# SCH_Clock_Iot.net
KiCad netlist of a schematic drawn in Altium Designer
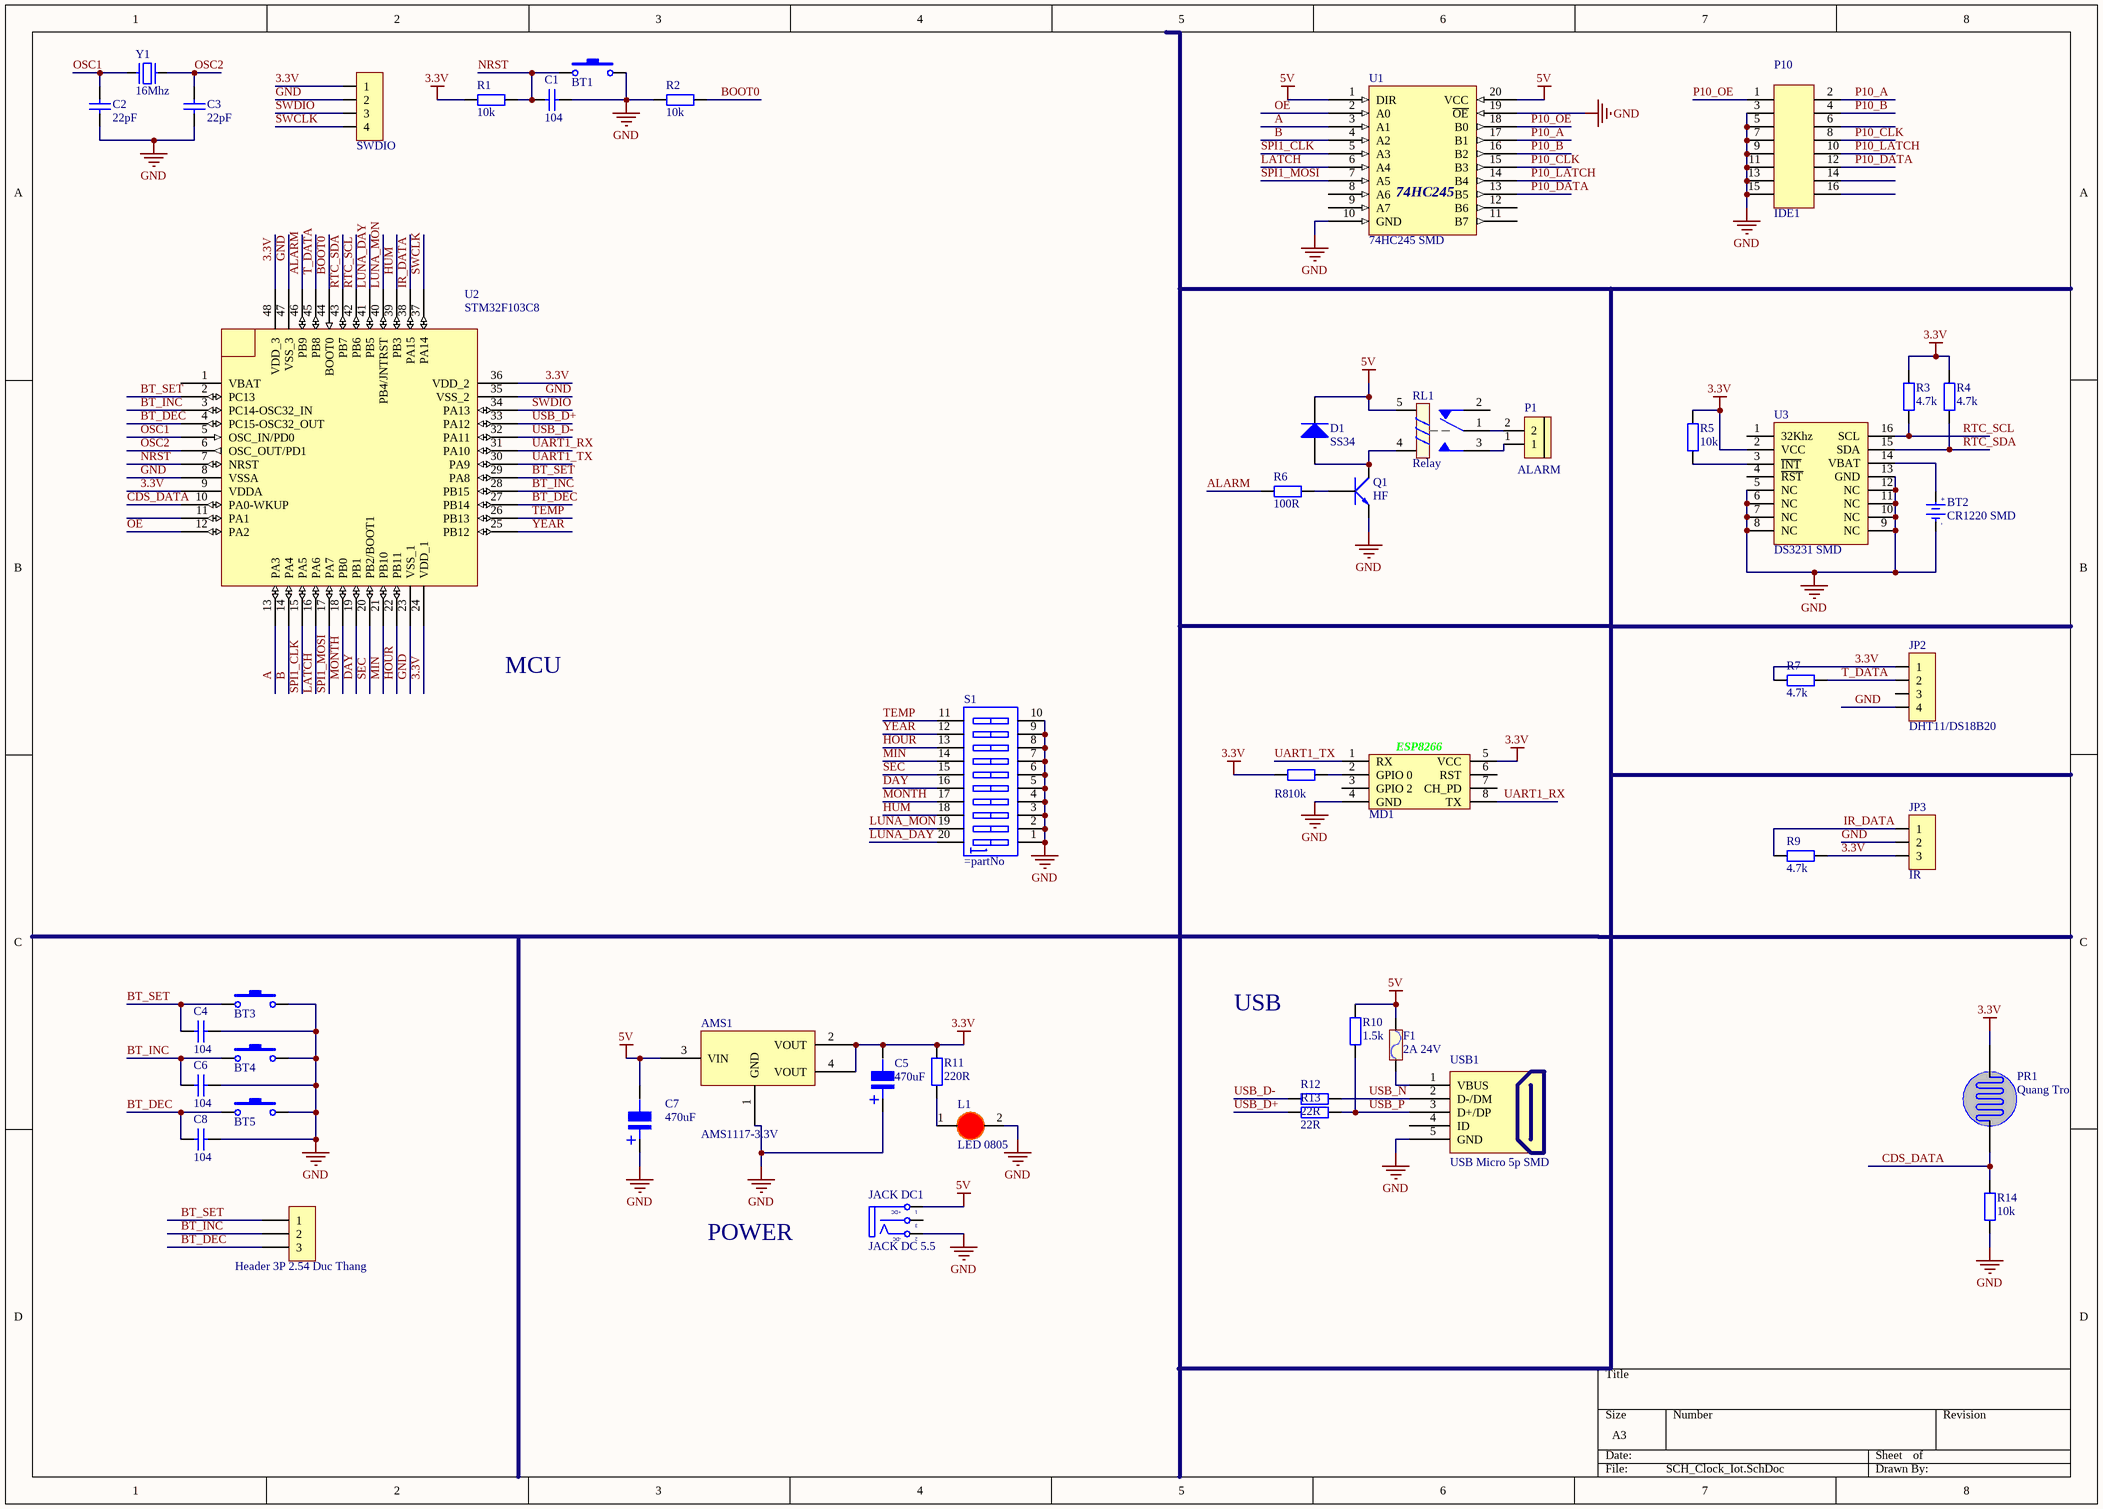
[diagram p0: SCH_Clock_Iot.SchDoc]

(export (version "E")
  (design (tool "Eeschema 10.0.6"))
  (components
    (comp (ref "AMS1")
      (value "AMS1117-3.3V")
      (footprint "SOT223")
      (description "Dán")
      (libsource (lib "Altium_Lib_by_KhueNguyenCreator") (part "AMS1117 SMD"))
    )
    (comp (ref "BT1")
      (value "Nut Nhan 2 Chan SMD 3x6x2.5")
      (footprint "Nut Nhan 2 Chan SMD 3x6x2.5")
      (libsource (lib "Altium_Lib_by_KhueNguyenCreator") (part "Nut Nhan 2 Chan SMD 3x6x2.5"))
    )
    (comp (ref "BT2")
      (value "CR1220 SMD")
      (footprint "DE PIN CR1220")
      (libsource (lib "Altium_Lib_by_KhueNguyenCreator") (part "De pin CR1220 SMD"))
    )
    (comp (ref "BT3")
      (value "Nut Nhan 2 Chan SMD 3x6x2.5")
      (footprint "Nut Nhan 2 Chan SMD 3x6x2.5")
      (libsource (lib "Altium_Lib_by_KhueNguyenCreator") (part "Nut Nhan 2 Chan SMD 3x6x2.5"))
    )
    (comp (ref "BT4")
      (value "Nut Nhan 2 Chan SMD 3x6x2.5")
      (footprint "Nut Nhan 2 Chan SMD 3x6x2.5")
      (libsource (lib "Altium_Lib_by_KhueNguyenCreator") (part "Nut Nhan 2 Chan SMD 3x6x2.5"))
    )
    (comp (ref "BT5")
      (value "Nut Nhan 2 Chan SMD 3x6x2.5")
      (footprint "Nut Nhan 2 Chan SMD 3x6x2.5")
      (libsource (lib "Altium_Lib_by_KhueNguyenCreator") (part "Nut Nhan 2 Chan SMD 3x6x2.5"))
    )
    (comp (ref "C1")
      (value "104")
      (footprint "tu 0805")
      (description "Dán")
      (libsource (lib "Altium_Lib_by_KhueNguyenCreator") (part "Tu 0805 104 50V 10%"))
    )
    (comp (ref "C2")
      (value "22pF")
      (footprint "tu 0805")
      (description "Dán")
      (libsource (lib "Altium_Lib_by_KhueNguyenCreator") (part "Tu 0805 22pF 50V 10%"))
    )
    (comp (ref "C3")
      (value "22pF")
      (footprint "tu 0805")
      (description "Dán")
      (libsource (lib "Altium_Lib_by_KhueNguyenCreator") (part "Tu 0805 22pF 50V 10%"))
    )
    (comp (ref "C4")
      (value "104")
      (footprint "tu 0805")
      (description "Dán")
      (libsource (lib "Altium_Lib_by_KhueNguyenCreator") (part "Tu 0805 104 50V 10%"))
    )
    (comp (ref "C5")
      (value "470uF")
      (footprint "tu nhom 8 (f)")
      (description "Dán")
      (libsource (lib "Altium_Lib_by_KhueNguyenCreator") (part "Tu Nhom 470uF 16V"))
    )
    (comp (ref "C6")
      (value "104")
      (footprint "tu 0805")
      (description "Dán")
      (libsource (lib "Altium_Lib_by_KhueNguyenCreator") (part "Tu 0805 104 50V 10%"))
    )
    (comp (ref "C7")
      (value "470uF")
      (footprint "tu nhom 8 (f)")
      (description "Dán")
      (libsource (lib "Altium_Lib_by_KhueNguyenCreator") (part "Tu Nhom 470uF 16V"))
    )
    (comp (ref "C8")
      (value "104")
      (footprint "tu 0805")
      (description "Dán")
      (libsource (lib "Altium_Lib_by_KhueNguyenCreator") (part "Tu 0805 104 50V 10%"))
    )
    (comp (ref "D1")
      (value "SS34")
      (footprint "DIODE SMA")
      (description "Dán")
      (libsource (lib "Altium_Lib_by_KhueNguyenCreator") (part "Diode SS34 ( 1N5822 )"))
    )
    (comp (ref "F1")
      (value "2A 24V")
      (footprint "Cau chi tu phuc hoi 2A 24V SMD1812")
      (description "2A 24V SMD1812")
      (libsource (lib "Altium_Lib_by_KhueNguyenCreator") (part "Cau chi tu phuc hoi 2A 24V SMD1812"))
    )
    (comp (ref "H1")
      (value "Header 3P 2.54 Duc Thang")
      (footprint "Header DT 3P_2.54")
      (description "Cắm")
      (libsource (lib "Altium_Lib_by_KhueNguyenCreator") (part "Header 3P 2.54 Duc Thang"))
    )
    (comp (ref "IDE1")
      (value "P10")
      (footprint "IDE16 DT")
      (libsource (lib "Altium_Lib_by_KhueNguyenCreator") (part "IDE 16 DT"))
    )
    (comp (ref "JACK DC1")
      (value "JACK DC 5.5")
      (footprint "JACK DC 5.5")
      (libsource (lib "Altium_Lib_by_KhueNguyenCreator") (part "JACK DC 5.5"))
    )
    (comp (ref "JP1")
      (value "SWDIO")
      (footprint "JP 1x4 DT")
      (description "Cắm")
      (libsource (lib "Altium_Lib_by_KhueNguyenCreator") (part "JP 1x4 2.54 Duc Thang"))
    )
    (comp (ref "JP2")
      (value "DHT11/DS18B20")
      (footprint "JP 1x4 CT")
      (description "Cắm")
      (libsource (lib "Altium_Lib_by_KhueNguyenCreator") (part "JP 1x4 2.54 Cai Thang"))
    )
    (comp (ref "JP3")
      (value "IR")
      (footprint "JP 1x3 CT")
      (description "Cắm")
      (libsource (lib "Altium_Lib_by_KhueNguyenCreator") (part "JP 1x3 2.54 Cai Thang"))
    )
    (comp (ref "L1")
      (value "LED 0805")
      (footprint "LED-0805-Red")
      (description "Dán")
      (libsource (lib "Altium_Lib_by_KhueNguyenCreator") (part "LED 0805 Do"))
    )
    (comp (ref "MD1")
      (value "ESP8266 Module")
      (footprint "ESP2866 Module")
      (libsource (lib "Altium_Lib_by_KhueNguyenCreator") (part "ESP8266 Module"))
    )
    (comp (ref "P1")
      (value "ALARM")
      (footprint "CON 2 2EDG5.08")
      (description "Cắm")
      (libsource (lib "Altium_Lib_by_KhueNguyenCreator") (part "CON 2 EDG5.08"))
    )
    (comp (ref "PR1")
      (value "Quang Tro")
      (footprint "Quang Tro")
      (description "Photoresistor")
      (fields (field (name "CREATOR") "Bien Nguyen"))
      (libsource (lib "Altium_Lib_by_KhueNguyenCreator") (part "Quang Tro"))
    )
    (comp (ref "Q1")
      (value "HF")
      (footprint "SOT23")
      (description "NPN transistor")
      (libsource (lib "Altium_Lib_by_KhueNguyenCreator") (part "C1815 HF SMD"))
    )
    (comp (ref "R1")
      (value "10k")
      (footprint "tro smd 0805")
      (description "Dán")
      (libsource (lib "Altium_Lib_by_KhueNguyenCreator") (part "Tro 0805 5% 10k"))
    )
    (comp (ref "R2")
      (value "10k")
      (footprint "tro smd 0805")
      (description "Dán")
      (libsource (lib "Altium_Lib_by_KhueNguyenCreator") (part "Tro 0805 5% 10k"))
    )
    (comp (ref "R3")
      (value "4.7k")
      (footprint "tro smd 0805")
      (description "Dán")
      (libsource (lib "Altium_Lib_by_KhueNguyenCreator") (part "Tro 0805 5% 4.7k"))
    )
    (comp (ref "R4")
      (value "4.7k")
      (footprint "tro smd 0805")
      (description "Dán")
      (libsource (lib "Altium_Lib_by_KhueNguyenCreator") (part "Tro 0805 5% 4.7k"))
    )
    (comp (ref "R5")
      (value "10k")
      (footprint "tro smd 0805")
      (description "Dán")
      (libsource (lib "Altium_Lib_by_KhueNguyenCreator") (part "Tro 0805 5% 10k"))
    )
    (comp (ref "R6")
      (value "100R")
      (footprint "tro smd 0805")
      (description "Dán")
      (libsource (lib "Altium_Lib_by_KhueNguyenCreator") (part "Tro 0805 5% 100R"))
    )
    (comp (ref "R7")
      (value "4.7k")
      (footprint "tro smd 0805")
      (description "Dán")
      (libsource (lib "Altium_Lib_by_KhueNguyenCreator") (part "Tro 0805 5% 4.7k"))
    )
    (comp (ref "R8")
      (value "10k")
      (footprint "tro smd 0805")
      (description "Dán")
      (libsource (lib "Altium_Lib_by_KhueNguyenCreator") (part "Tro 0805 5% 10k"))
    )
    (comp (ref "R9")
      (value "4.7k")
      (footprint "tro smd 0805")
      (description "Dán")
      (libsource (lib "Altium_Lib_by_KhueNguyenCreator") (part "Tro 0805 5% 4.7k"))
    )
    (comp (ref "R10")
      (value "1.5k")
      (footprint "tro smd 0805")
      (description "Dán")
      (libsource (lib "Altium_Lib_by_KhueNguyenCreator") (part "Tro 0805 5% 1.5k"))
    )
    (comp (ref "R11")
      (value "220R")
      (footprint "tro smd 0805")
      (description "Dán")
      (libsource (lib "Altium_Lib_by_KhueNguyenCreator") (part "Tro 0805 5% 220R"))
    )
    (comp (ref "R12")
      (value "22R")
      (footprint "tro smd 0805")
      (description "Dán")
      (libsource (lib "Altium_Lib_by_KhueNguyenCreator") (part "Tro 0805 5% 22R"))
    )
    (comp (ref "R13")
      (value "22R")
      (footprint "tro smd 0805")
      (description "Dán")
      (libsource (lib "Altium_Lib_by_KhueNguyenCreator") (part "Tro 0805 5% 22R"))
    )
    (comp (ref "R14")
      (value "10k")
      (footprint "tro smd 0805")
      (description "Dán")
      (libsource (lib "Altium_Lib_by_KhueNguyenCreator") (part "Tro 0805 5% 10k"))
    )
    (comp (ref "RL1")
      (value "Relay")
      (footprint "Relay 5 Chan SRD")
      (description "Relay 5 Chan")
      (libsource (lib "Altium_Lib_by_KhueNguyenCreator") (part "Relay 5 Chan SRD"))
    )
    (comp (ref "S1")
      (value "~")
      (footprint "SW-DIP10-1")
      (description "WS-DITV 2.54 mm small compact THT flat actuator with top tape")
      (fields
        (field (name "MANUFACTURER") "Wurth Elektronik")
        (field (name "PART NO.") "418127160910")
        (field (name "CREATED BY") "Baojun Chen")
      )
      (libsource (lib "Thu Vien Chuan MH") (part "SWDIP10"))
    )
    (comp (ref "U1")
      (value "74HC245 SMD")
      (footprint "TSSOP20")
      (description "Dán")
      (libsource (lib "Altium_Lib_by_KhueNguyenCreator") (part "74HC245 SMD"))
    )
    (comp (ref "U2")
      (value "STM32F103C8")
      (footprint "STM32_LQPF48")
      (fields (field (name "PUBLISHER") "Altium Limited"))
      (libsource (lib "Altium_Lib_by_KhueNguyenCreator") (part "STM32F103xx_LQFP48"))
    )
    (comp (ref "U3")
      (value "DS3231 SMD")
      (footprint "SOIC 16")
      (description "SOIC")
      (libsource (lib "Altium_Lib_by_KhueNguyenCreator") (part "DS3231 SMD"))
    )
    (comp (ref "USB1")
      (value "USB Micro 5p SMD")
      (footprint "USB Micro 5p SMD")
      (description "USB Type B")
      (libsource (lib "Altium_Lib_by_KhueNguyenCreator") (part "USB Micro 5p SMD"))
    )
    (comp (ref "Y1")
      (value "16Mhz")
      (footprint "Thach Anh 2 chan cam")
      (description "Crystal For all Crystal 2pin.")
      (libsource (lib "Altium_Lib_by_KhueNguyenCreator") (part "Thach Anh 2 chan Cam"))
    )
  )
  (nets
    (net (code "1") (name "/A") (class "Default")
      (node (ref "U1") (pin "3") (pinfunction "A1_3") (pintype "input"))
      (node (ref "U2") (pin "13") (pinfunction "PA3_13") (pintype "bidirectional"))
    )
    (net (code "2") (name "/ALARM") (class "Default")
      (node (ref "R6") (pin "1") (pinfunction "1_1") (pintype "passive"))
      (node (ref "U2") (pin "46") (pinfunction "PB9_46") (pintype "bidirectional"))
    )
    (net (code "3") (name "/B") (class "Default")
      (node (ref "U1") (pin "4") (pinfunction "A2_4") (pintype "input"))
      (node (ref "U2") (pin "14") (pinfunction "PA4_14") (pintype "bidirectional"))
    )
    (net (code "4") (name "/BOOT0") (class "Default")
      (node (ref "R2") (pin "1") (pinfunction "1_1") (pintype "passive"))
      (node (ref "U2") (pin "44") (pinfunction "BOOT0_44") (pintype "input"))
    )
    (net (code "5") (name "/BT_DEC") (class "Default")
      (node (ref "BT5") (pin "1") (pinfunction "1_1") (pintype "passive"))
      (node (ref "C8") (pin "1") (pinfunction "1_1") (pintype "passive"))
      (node (ref "H1") (pin "3") (pinfunction "3_3") (pintype "passive"))
      (node (ref "U2") (pin "27") (pinfunction "PB14_27") (pintype "bidirectional"))
      (node (ref "U2") (pin "4") (pinfunction "PC15-OSC32_OUT_4") (pintype "bidirectional"))
    )
    (net (code "6") (name "/BT_INC") (class "Default")
      (node (ref "BT4") (pin "1") (pinfunction "1_1") (pintype "passive"))
      (node (ref "C6") (pin "1") (pinfunction "1_1") (pintype "passive"))
      (node (ref "H1") (pin "2") (pinfunction "2_2") (pintype "passive"))
      (node (ref "U2") (pin "28") (pinfunction "PB15_28") (pintype "bidirectional"))
      (node (ref "U2") (pin "3") (pinfunction "PC14-OSC32_IN_3") (pintype "bidirectional"))
    )
    (net (code "7") (name "/BT_SET") (class "Default")
      (node (ref "BT3") (pin "1") (pinfunction "1_1") (pintype "passive"))
      (node (ref "C4") (pin "1") (pinfunction "1_1") (pintype "passive"))
      (node (ref "H1") (pin "1") (pinfunction "1_1") (pintype "passive"))
      (node (ref "U2") (pin "2") (pinfunction "PC13_2") (pintype "bidirectional"))
      (node (ref "U2") (pin "29") (pinfunction "PA8_29") (pintype "bidirectional"))
    )
    (net (code "8") (name "/CDS_DATA") (class "Default")
      (node (ref "PR1") (pin "1") (pinfunction "1_1") (pintype "passive"))
      (node (ref "R14") (pin "2") (pinfunction "2_2") (pintype "passive"))
      (node (ref "U2") (pin "10") (pinfunction "PA0-WKUP_10") (pintype "bidirectional"))
    )
    (net (code "9") (name "/DAY") (class "Default")
      (node (ref "S1") (pin "16") (pinfunction "16_16") (pintype "passive"))
      (node (ref "U2") (pin "19") (pinfunction "PB1_19") (pintype "bidirectional"))
    )
    (net (code "10") (name "/HOUR") (class "Default")
      (node (ref "S1") (pin "13") (pinfunction "13_13") (pintype "passive"))
      (node (ref "U2") (pin "22") (pinfunction "PB11_22") (pintype "bidirectional"))
    )
    (net (code "11") (name "/HUM") (class "Default")
      (node (ref "S1") (pin "18") (pinfunction "18_18") (pintype "passive"))
      (node (ref "U2") (pin "39") (pinfunction "PB3_39") (pintype "bidirectional"))
    )
    (net (code "12") (name "/IR_DATA") (class "Default")
      (node (ref "JP3") (pin "1") (pinfunction "1_1") (pintype "passive"))
      (node (ref "R9") (pin "2") (pinfunction "2_2") (pintype "passive"))
      (node (ref "U2") (pin "38") (pinfunction "PA15_38") (pintype "bidirectional"))
    )
    (net (code "13") (name "/LATCH") (class "Default")
      (node (ref "U1") (pin "6") (pinfunction "A4_6") (pintype "input"))
      (node (ref "U2") (pin "16") (pinfunction "PA6_16") (pintype "bidirectional"))
    )
    (net (code "14") (name "/LUNA_DAY") (class "Default")
      (node (ref "S1") (pin "20") (pinfunction "20_20") (pintype "passive"))
      (node (ref "U2") (pin "41") (pinfunction "PB5_41") (pintype "bidirectional"))
    )
    (net (code "15") (name "/LUNA_MON") (class "Default")
      (node (ref "S1") (pin "19") (pinfunction "19_19") (pintype "passive"))
      (node (ref "U2") (pin "40") (pinfunction "PB4/JNTRST_40") (pintype "bidirectional"))
    )
    (net (code "16") (name "/MIN") (class "Default")
      (node (ref "S1") (pin "14") (pinfunction "14_14") (pintype "passive"))
      (node (ref "U2") (pin "21") (pinfunction "PB10_21") (pintype "bidirectional"))
    )
    (net (code "17") (name "/MONTH") (class "Default")
      (node (ref "S1") (pin "17") (pinfunction "17_17") (pintype "passive"))
      (node (ref "U2") (pin "18") (pinfunction "PB0_18") (pintype "bidirectional"))
    )
    (net (code "18") (name "/NRST") (class "Default")
      (node (ref "BT1") (pin "1") (pinfunction "1_1") (pintype "passive"))
      (node (ref "C1") (pin "1") (pinfunction "1_1") (pintype "passive"))
      (node (ref "R1") (pin "1") (pinfunction "1_1") (pintype "passive"))
      (node (ref "U2") (pin "7") (pinfunction "NRST_7") (pintype "bidirectional"))
    )
    (net (code "19") (name "/OE") (class "Default")
      (node (ref "U1") (pin "2") (pinfunction "A0_2") (pintype "input"))
      (node (ref "U2") (pin "12") (pinfunction "PA2_12") (pintype "bidirectional"))
    )
    (net (code "20") (name "/OSC1") (class "Default")
      (node (ref "C2") (pin "1") (pinfunction "1_1") (pintype "passive"))
      (node (ref "U2") (pin "5") (pinfunction "OSC_IN/PD0_5") (pintype "input"))
      (node (ref "Y1") (pin "1") (pinfunction "1_1") (pintype "passive"))
    )
    (net (code "21") (name "/OSC2") (class "Default")
      (node (ref "C3") (pin "1") (pinfunction "1_1") (pintype "passive"))
      (node (ref "U2") (pin "6") (pinfunction "OSC_OUT/PD1_6") (pintype "output"))
      (node (ref "Y1") (pin "2") (pinfunction "2_2") (pintype "passive"))
    )
    (net (code "22") (name "/P10_A") (class "Default")
      (node (ref "IDE1") (pin "2") (pinfunction "2_2") (pintype "passive"))
      (node (ref "U1") (pin "17") (pinfunction "B1_17") (pintype "output"))
    )
    (net (code "23") (name "/P10_B") (class "Default")
      (node (ref "IDE1") (pin "4") (pinfunction "4_4") (pintype "passive"))
      (node (ref "U1") (pin "16") (pinfunction "B2_16") (pintype "output"))
    )
    (net (code "24") (name "/P10_CLK") (class "Default")
      (node (ref "IDE1") (pin "8") (pinfunction "8_8") (pintype "passive"))
      (node (ref "U1") (pin "15") (pinfunction "B3_15") (pintype "output"))
    )
    (net (code "25") (name "/P10_DATA") (class "Default")
      (node (ref "IDE1") (pin "12") (pinfunction "12_12") (pintype "passive"))
      (node (ref "U1") (pin "13") (pinfunction "B5_13") (pintype "output"))
    )
    (net (code "26") (name "/P10_LATCH") (class "Default")
      (node (ref "IDE1") (pin "10") (pinfunction "10_10") (pintype "passive"))
      (node (ref "U1") (pin "14") (pinfunction "B4_14") (pintype "output"))
    )
    (net (code "27") (name "/P10_OE") (class "Default")
      (node (ref "IDE1") (pin "1") (pinfunction "1_1") (pintype "passive"))
      (node (ref "U1") (pin "18") (pinfunction "B0_18") (pintype "output"))
    )
    (net (code "28") (name "/RTC_SCL") (class "Default")
      (node (ref "R3") (pin "1") (pinfunction "1_1") (pintype "passive"))
      (node (ref "U2") (pin "42") (pinfunction "PB6_42") (pintype "bidirectional"))
      (node (ref "U3") (pin "16") (pinfunction "SCL_16") (pintype "power_in"))
    )
    (net (code "29") (name "/RTC_SDA") (class "Default")
      (node (ref "R4") (pin "1") (pinfunction "1_1") (pintype "passive"))
      (node (ref "U2") (pin "43") (pinfunction "PB7_43") (pintype "bidirectional"))
      (node (ref "U3") (pin "15") (pinfunction "SDA_15") (pintype "power_in"))
    )
    (net (code "30") (name "/SEC") (class "Default")
      (node (ref "S1") (pin "15") (pinfunction "15_15") (pintype "passive"))
      (node (ref "U2") (pin "20") (pinfunction "PB2/BOOT1_20") (pintype "bidirectional"))
    )
    (net (code "31") (name "/SPI1_CLK") (class "Default")
      (node (ref "U1") (pin "5") (pinfunction "A3_5") (pintype "input"))
      (node (ref "U2") (pin "15") (pinfunction "PA5_15") (pintype "bidirectional"))
    )
    (net (code "32") (name "/SPI1_MOSI") (class "Default")
      (node (ref "U1") (pin "7") (pinfunction "A5_7") (pintype "input"))
      (node (ref "U2") (pin "17") (pinfunction "PA7_17") (pintype "bidirectional"))
    )
    (net (code "33") (name "/SWCLK") (class "Default")
      (node (ref "JP1") (pin "4") (pinfunction "4_4") (pintype "passive"))
      (node (ref "U2") (pin "37") (pinfunction "PA14_37") (pintype "bidirectional"))
    )
    (net (code "34") (name "/SWDIO") (class "Default")
      (node (ref "JP1") (pin "3") (pinfunction "3_3") (pintype "passive"))
      (node (ref "U2") (pin "34") (pinfunction "PA13_34") (pintype "bidirectional"))
    )
    (net (code "35") (name "/TEMP") (class "Default")
      (node (ref "S1") (pin "11") (pinfunction "11_11") (pintype "passive"))
      (node (ref "U2") (pin "26") (pinfunction "PB13_26") (pintype "bidirectional"))
    )
    (net (code "36") (name "/T_DATA") (class "Default")
      (node (ref "JP2") (pin "2") (pinfunction "2_2") (pintype "passive"))
      (node (ref "R7") (pin "1") (pinfunction "1_1") (pintype "passive"))
      (node (ref "U2") (pin "45") (pinfunction "PB8_45") (pintype "bidirectional"))
    )
    (net (code "37") (name "/UART1_RX") (class "Default")
      (node (ref "MD1") (pin "8") (pinfunction "TX_8") (pintype "passive"))
      (node (ref "U2") (pin "31") (pinfunction "PA10_31") (pintype "bidirectional"))
    )
    (net (code "38") (name "/UART1_TX") (class "Default")
      (node (ref "MD1") (pin "1") (pinfunction "RX_1") (pintype "passive"))
      (node (ref "U2") (pin "30") (pinfunction "PA9_30") (pintype "bidirectional"))
    )
    (net (code "39") (name "/USB_D+") (class "Default")
      (node (ref "R13") (pin "1") (pinfunction "1_1") (pintype "passive"))
      (node (ref "U2") (pin "33") (pinfunction "PA12_33") (pintype "bidirectional"))
    )
    (net (code "40") (name "/USB_D-") (class "Default")
      (node (ref "R12") (pin "1") (pinfunction "1_1") (pintype "passive"))
      (node (ref "U2") (pin "32") (pinfunction "PA11_32") (pintype "bidirectional"))
    )
    (net (code "41") (name "/USB_N") (class "Default")
      (node (ref "R12") (pin "2") (pinfunction "2_2") (pintype "passive"))
      (node (ref "USB1") (pin "2") (pinfunction "D-/DM_2") (pintype "passive"))
    )
    (net (code "42") (name "/USB_P") (class "Default")
      (node (ref "R10") (pin "2") (pinfunction "2_2") (pintype "passive"))
      (node (ref "R13") (pin "2") (pinfunction "2_2") (pintype "passive"))
      (node (ref "USB1") (pin "3") (pinfunction "D+/DP_3") (pintype "passive"))
    )
    (net (code "43") (name "/YEAR") (class "Default")
      (node (ref "S1") (pin "12") (pinfunction "12_12") (pintype "passive"))
      (node (ref "U2") (pin "25") (pinfunction "PB12_25") (pintype "bidirectional"))
    )
    (net (code "44") (name "3.3V") (class "Default")
      (node (ref "AMS1") (pin "2") (pinfunction "VOUT_2") (pintype "passive"))
      (node (ref "AMS1") (pin "4") (pinfunction "VOUT_4") (pintype "passive"))
      (node (ref "C5") (pin "2") (pinfunction "2_2") (pintype "passive"))
      (node (ref "JP1") (pin "1") (pinfunction "1_1") (pintype "passive"))
      (node (ref "JP2") (pin "1") (pinfunction "1_1") (pintype "passive"))
      (node (ref "JP3") (pin "3") (pinfunction "3_3") (pintype "passive"))
      (node (ref "MD1") (pin "5") (pinfunction "VCC_5") (pintype "passive"))
      (node (ref "PR1") (pin "2") (pinfunction "2_2") (pintype "passive"))
      (node (ref "R1") (pin "2") (pinfunction "2_2") (pintype "passive"))
      (node (ref "R11") (pin "2") (pinfunction "2_2") (pintype "passive"))
      (node (ref "R3") (pin "2") (pinfunction "2_2") (pintype "passive"))
      (node (ref "R4") (pin "2") (pinfunction "2_2") (pintype "passive"))
      (node (ref "R5") (pin "2") (pinfunction "2_2") (pintype "passive"))
      (node (ref "R7") (pin "2") (pinfunction "2_2") (pintype "passive"))
      (node (ref "R8") (pin "2") (pinfunction "2_2") (pintype "passive"))
      (node (ref "R9") (pin "1") (pinfunction "1_1") (pintype "passive"))
      (node (ref "U2") (pin "24") (pinfunction "VDD_1_24") (pintype "power_in"))
      (node (ref "U2") (pin "36") (pinfunction "VDD_2_36") (pintype "power_in"))
      (node (ref "U2") (pin "48") (pinfunction "VDD_3_48") (pintype "power_in"))
      (node (ref "U2") (pin "9") (pinfunction "VDDA_9") (pintype "power_in"))
      (node (ref "U3") (pin "2") (pinfunction "VCC_2") (pintype "power_in"))
    )
    (net (code "45") (name "5V") (class "Default")
      (node (ref "AMS1") (pin "3") (pinfunction "VIN_3") (pintype "passive"))
      (node (ref "C7") (pin "2") (pinfunction "2_2") (pintype "passive"))
      (node (ref "D1") (pin "2") (pinfunction "K_2") (pintype "passive"))
      (node (ref "F1") (pin "2") (pinfunction "2_2") (pintype "passive"))
      (node (ref "JACK DC1") (pin "1") (pinfunction "T_1") (pintype "passive"))
      (node (ref "R10") (pin "1") (pinfunction "1_1") (pintype "passive"))
      (node (ref "RL1") (pin "5") (pinfunction "5_5") (pintype "passive"))
      (node (ref "U1") (pin "1") (pinfunction "DIR_1") (pintype "input"))
      (node (ref "U1") (pin "20") (pinfunction "VCC_20") (pintype "input"))
    )
    (net (code "46") (name "GND") (class "Default")
      (node (ref "AMS1") (pin "1") (pinfunction "GND_1") (pintype "passive"))
      (node (ref "BT1") (pin "2") (pinfunction "2_2") (pintype "passive"))
      (node (ref "BT2") (pin "2") (pinfunction "GND_2") (pintype "passive"))
      (node (ref "BT3") (pin "2") (pinfunction "2_2") (pintype "passive"))
      (node (ref "BT4") (pin "2") (pinfunction "2_2") (pintype "passive"))
      (node (ref "BT5") (pin "2") (pinfunction "2_2") (pintype "passive"))
      (node (ref "C1") (pin "2") (pinfunction "2_2") (pintype "passive"))
      (node (ref "C2") (pin "2") (pinfunction "2_2") (pintype "passive"))
      (node (ref "C3") (pin "2") (pinfunction "2_2") (pintype "passive"))
      (node (ref "C4") (pin "2") (pinfunction "2_2") (pintype "passive"))
      (node (ref "C5") (pin "1") (pinfunction "1_1") (pintype "passive"))
      (node (ref "C6") (pin "2") (pinfunction "2_2") (pintype "passive"))
      (node (ref "C7") (pin "1") (pinfunction "1_1") (pintype "passive"))
      (node (ref "C8") (pin "2") (pinfunction "2_2") (pintype "passive"))
      (node (ref "IDE1") (pin "11") (pinfunction "11_11") (pintype "passive"))
      (node (ref "IDE1") (pin "13") (pinfunction "13_13") (pintype "passive"))
      (node (ref "IDE1") (pin "15") (pinfunction "14_15") (pintype "passive"))
      (node (ref "IDE1") (pin "3") (pinfunction "3_3") (pintype "passive"))
      (node (ref "IDE1") (pin "5") (pinfunction "5_5") (pintype "passive"))
      (node (ref "IDE1") (pin "7") (pinfunction "7_7") (pintype "passive"))
      (node (ref "IDE1") (pin "9") (pinfunction "9_9") (pintype "passive"))
      (node (ref "JACK DC1") (pin "2") (pinfunction "TN_2") (pintype "passive"))
      (node (ref "JP1") (pin "2") (pinfunction "2_2") (pintype "passive"))
      (node (ref "JP2") (pin "4") (pinfunction "4_4") (pintype "passive"))
      (node (ref "JP3") (pin "2") (pinfunction "2_2") (pintype "passive"))
      (node (ref "L1") (pin "2") (pinfunction "K_2") (pintype "passive"))
      (node (ref "MD1") (pin "4") (pinfunction "GND_4") (pintype "passive"))
      (node (ref "Q1") (pin "2") (pinfunction "E_2") (pintype "passive"))
      (node (ref "R14") (pin "1") (pinfunction "1_1") (pintype "passive"))
      (node (ref "R2") (pin "2") (pinfunction "2_2") (pintype "passive"))
      (node (ref "S1") (pin "1") (pinfunction "1_1") (pintype "passive"))
      (node (ref "S1") (pin "10") (pinfunction "10_10") (pintype "passive"))
      (node (ref "S1") (pin "2") (pinfunction "2_2") (pintype "passive"))
      (node (ref "S1") (pin "3") (pinfunction "3_3") (pintype "passive"))
      (node (ref "S1") (pin "4") (pinfunction "4_4") (pintype "passive"))
      (node (ref "S1") (pin "5") (pinfunction "5_5") (pintype "passive"))
      (node (ref "S1") (pin "6") (pinfunction "6_6") (pintype "passive"))
      (node (ref "S1") (pin "7") (pinfunction "7_7") (pintype "passive"))
      (node (ref "S1") (pin "8") (pinfunction "8_8") (pintype "passive"))
      (node (ref "S1") (pin "9") (pinfunction "9_9") (pintype "passive"))
      (node (ref "U1") (pin "10") (pinfunction "GND_10") (pintype "input"))
      (node (ref "U1") (pin "19") (pinfunction "~{OE}_19") (pintype "input"))
      (node (ref "U2") (pin "23") (pinfunction "VSS_1_23") (pintype "power_in"))
      (node (ref "U2") (pin "35") (pinfunction "VSS_2_35") (pintype "power_in"))
      (node (ref "U2") (pin "47") (pinfunction "VSS_3_47") (pintype "power_in"))
      (node (ref "U2") (pin "8") (pinfunction "VSSA_8") (pintype "power_in"))
      (node (ref "U3") (pin "10") (pinfunction "NC_10") (pintype "power_in"))
      (node (ref "U3") (pin "11") (pinfunction "NC_11") (pintype "power_in"))
      (node (ref "U3") (pin "12") (pinfunction "NC_12") (pintype "power_in"))
      (node (ref "U3") (pin "13") (pinfunction "GND_13") (pintype "power_in"))
      (node (ref "U3") (pin "5") (pinfunction "NC_5") (pintype "power_in"))
      (node (ref "U3") (pin "6") (pinfunction "NC_6") (pintype "power_in"))
      (node (ref "U3") (pin "7") (pinfunction "NC_7") (pintype "power_in"))
      (node (ref "U3") (pin "8") (pinfunction "NC_8") (pintype "power_in"))
      (node (ref "U3") (pin "9") (pinfunction "NC_9") (pintype "power_in"))
      (node (ref "USB1") (pin "5") (pinfunction "GND_5") (pintype "passive"))
    )
    (net (code "47") (name "Net-(BT2-+3V)") (class "Default")
      (node (ref "BT2") (pin "1") (pinfunction "+3V_1") (pintype "passive"))
      (node (ref "U3") (pin "14") (pinfunction "VBAT_14") (pintype "power_in"))
    )
    (net (code "48") (name "Net-(D1-A)") (class "Default")
      (node (ref "D1") (pin "1") (pinfunction "A_1") (pintype "passive"))
      (node (ref "Q1") (pin "3") (pinfunction "C_3") (pintype "passive"))
      (node (ref "RL1") (pin "4") (pinfunction "4_4") (pintype "passive"))
    )
    (net (code "49") (name "Net-(L1-A)") (class "Default")
      (node (ref "L1") (pin "1") (pinfunction "A_1") (pintype "passive"))
      (node (ref "R11") (pin "1") (pinfunction "1_1") (pintype "passive"))
    )
    (net (code "50") (name "Net-(MD1-GPIO_0)") (class "Default")
      (node (ref "MD1") (pin "2") (pinfunction "GPIO_0_2") (pintype "passive"))
      (node (ref "R8") (pin "1") (pinfunction "1_1") (pintype "passive"))
    )
    (net (code "51") (name "Net-(P1-Pad1)") (class "Default")
      (node (ref "P1") (pin "1") (pinfunction "1_1") (pintype "passive"))
      (node (ref "RL1") (pin "3") (pinfunction "3_3") (pintype "passive"))
    )
    (net (code "52") (name "Net-(P1-Pad2)") (class "Default")
      (node (ref "P1") (pin "2") (pinfunction "2_2") (pintype "passive"))
      (node (ref "RL1") (pin "1") (pinfunction "1_1") (pintype "passive"))
    )
    (net (code "53") (name "Net-(Q1-B)") (class "Default")
      (node (ref "Q1") (pin "1") (pinfunction "B_1") (pintype "passive"))
      (node (ref "R6") (pin "2") (pinfunction "2_2") (pintype "passive"))
    )
    (net (code "54") (name "Net-(U3-~{INT})") (class "Default")
      (node (ref "R5") (pin "1") (pinfunction "1_1") (pintype "passive"))
      (node (ref "U3") (pin "3") (pinfunction "~{INT}_3") (pintype "power_in"))
    )
    (net (code "55") (name "Net-(USB1-VBUS)") (class "Default")
      (node (ref "F1") (pin "1") (pinfunction "1_1") (pintype "passive"))
      (node (ref "USB1") (pin "1") (pinfunction "VBUS_1") (pintype "passive"))
    )
    (net (code "56") (name "unconnected-(IDE1-14-Pad16)") (class "Default")
      (node (ref "IDE1") (pin "16") (pinfunction "14_16") (pintype "passive"))
    )
    (net (code "57") (name "unconnected-(IDE1-Pad6)") (class "Default")
      (node (ref "IDE1") (pin "6") (pinfunction "6_6") (pintype "passive"))
    )
    (net (code "58") (name "unconnected-(IDE1-Pad14)") (class "Default")
      (node (ref "IDE1") (pin "14") (pinfunction "14_14") (pintype "passive"))
    )
    (net (code "59") (name "unconnected-(JACK DC1-S-Pad3)") (class "Default")
      (node (ref "JACK DC1") (pin "3") (pinfunction "S_3") (pintype "power_in"))
    )
    (net (code "60") (name "unconnected-(JP2-Pad3)") (class "Default")
      (node (ref "JP2") (pin "3") (pinfunction "3_3") (pintype "passive"))
    )
    (net (code "61") (name "unconnected-(MD1-CH_PD-Pad7)") (class "Default")
      (node (ref "MD1") (pin "7") (pinfunction "CH_PD_7") (pintype "passive"))
    )
    (net (code "62") (name "unconnected-(MD1-GPIO_2-Pad3)") (class "Default")
      (node (ref "MD1") (pin "3") (pinfunction "GPIO_2_3") (pintype "passive"))
    )
    (net (code "63") (name "unconnected-(MD1-RST-Pad6)") (class "Default")
      (node (ref "MD1") (pin "6") (pinfunction "RST_6") (pintype "passive"))
    )
    (net (code "64") (name "unconnected-(RL1-Pad2)") (class "Default")
      (node (ref "RL1") (pin "2") (pinfunction "2_2") (pintype "passive"))
    )
    (net (code "65") (name "unconnected-(U1-A6-Pad8)") (class "Default")
      (node (ref "U1") (pin "8") (pinfunction "A6_8") (pintype "input"))
    )
    (net (code "66") (name "unconnected-(U1-A7-Pad9)") (class "Default")
      (node (ref "U1") (pin "9") (pinfunction "A7_9") (pintype "input"))
    )
    (net (code "67") (name "unconnected-(U1-B6-Pad12)") (class "Default")
      (node (ref "U1") (pin "12") (pinfunction "B6_12") (pintype "output"))
    )
    (net (code "68") (name "unconnected-(U1-B7-Pad11)") (class "Default")
      (node (ref "U1") (pin "11") (pinfunction "B7_11") (pintype "output"))
    )
    (net (code "69") (name "unconnected-(U2-PA1-Pad11)") (class "Default")
      (node (ref "U2") (pin "11") (pinfunction "PA1_11") (pintype "bidirectional"))
    )
    (net (code "70") (name "unconnected-(U2-VBAT-Pad1)") (class "Default")
      (node (ref "U2") (pin "1") (pinfunction "VBAT_1") (pintype "power_in"))
    )
    (net (code "71") (name "unconnected-(U3-32Khz-Pad1)") (class "Default")
      (node (ref "U3") (pin "1") (pinfunction "32Khz_1") (pintype "power_in"))
    )
    (net (code "72") (name "unconnected-(U3-~{RST}-Pad4)") (class "Default")
      (node (ref "U3") (pin "4") (pinfunction "~{RST}_4") (pintype "power_in"))
    )
    (net (code "73") (name "unconnected-(USB1-ID-Pad4)") (class "Default")
      (node (ref "USB1") (pin "4") (pinfunction "ID_4") (pintype "passive"))
    )
  )
)
